# 2_interface.net
KiCad netlist of a schematic drawn in Altium Designer
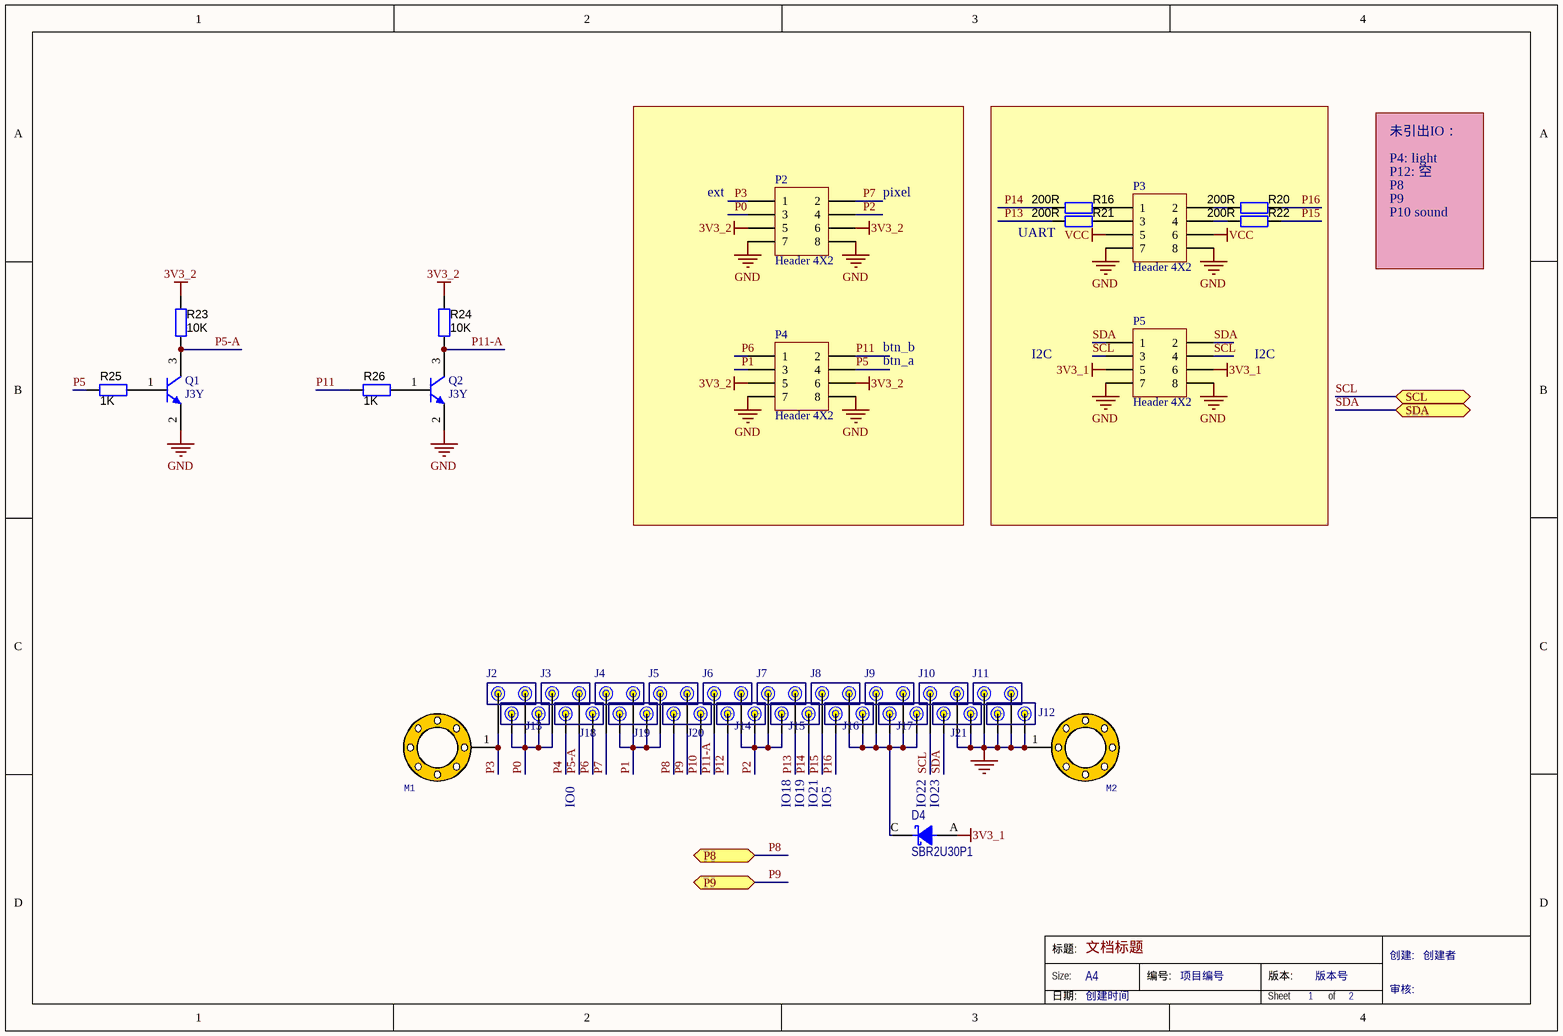
[diagram p0: 2.interface.SchDoc]

(export (version "E")
  (design (tool "Eeschema 10.0.6"))
  (components
    (comp (ref "D4")
      (value "SBR2U30P1")
      (footprint "POWERDI123")
      (fields (field (name "PARTNUMBER") "?") (field (name "PUBLISHER") "Altium Limited"))
      (libsource (lib "03.常用器件") (part "Diode_Schottky"))
    )
    (comp (ref "J2") (value "~") (footprint "顶针座子（2.54MM）") (libsource (lib "Schlib1") (part "pogopin")))
    (comp (ref "J3") (value "~") (footprint "顶针座子（2.54MM）") (libsource (lib "Schlib1") (part "pogopin")))
    (comp (ref "J4") (value "~") (footprint "顶针座子（2.54MM）") (libsource (lib "Schlib1") (part "pogopin")))
    (comp (ref "J5") (value "~") (footprint "顶针座子（2.54MM）") (libsource (lib "Schlib1") (part "pogopin")))
    (comp (ref "J6") (value "~") (footprint "顶针座子（2.54MM）") (libsource (lib "Schlib1") (part "pogopin")))
    (comp (ref "J7") (value "~") (footprint "顶针座子（2.54MM）") (libsource (lib "Schlib1") (part "pogopin")))
    (comp (ref "J8") (value "~") (footprint "顶针座子（2.54MM）") (libsource (lib "Schlib1") (part "pogopin")))
    (comp (ref "J9") (value "~") (footprint "顶针座子（2.54MM）") (libsource (lib "Schlib1") (part "pogopin")))
    (comp (ref "J10") (value "~") (footprint "顶针座子（2.54MM）") (libsource (lib "Schlib1") (part "pogopin")))
    (comp (ref "J11") (value "~") (footprint "顶针座子（2.54MM）") (libsource (lib "Schlib1") (part "pogopin")))
    (comp (ref "J12") (value "~") (footprint "顶针座子（2.54MM）") (libsource (lib "Schlib1") (part "pogopin_32")))
    (comp (ref "J13") (value "~") (footprint "顶针座子（2.54MM）") (libsource (lib "Schlib1") (part "pogopin_32")))
    (comp (ref "J14") (value "~") (footprint "顶针座子（2.54MM）") (libsource (lib "Schlib1") (part "pogopin_32")))
    (comp (ref "J15") (value "~") (footprint "顶针座子（2.54MM）") (libsource (lib "Schlib1") (part "pogopin_32")))
    (comp (ref "J16") (value "~") (footprint "顶针座子（2.54MM）") (libsource (lib "Schlib1") (part "pogopin_32")))
    (comp (ref "J17") (value "~") (footprint "顶针座子（2.54MM）") (libsource (lib "Schlib1") (part "pogopin_32")))
    (comp (ref "J18") (value "~") (footprint "顶针座子（2.54MM）") (libsource (lib "Schlib1") (part "pogopin_32")))
    (comp (ref "J19") (value "~") (footprint "顶针座子（2.54MM）") (libsource (lib "Schlib1") (part "pogopin_32")))
    (comp (ref "J20") (value "~") (footprint "顶针座子（2.54MM）") (libsource (lib "Schlib1") (part "pogopin_32")))
    (comp (ref "J21") (value "~") (footprint "顶针座子（2.54MM）") (libsource (lib "Schlib1") (part "pogopin_32")))
    (comp (ref "M1") (value "~") (footprint "3MM螺丝孔") (libsource (lib "labplus-connector") (part "screw")))
    (comp (ref "M2") (value "~") (footprint "3MM螺丝孔") (libsource (lib "labplus-connector") (part "screw")))
    (comp (ref "P2")
      (value "Header 4X2")
      (footprint "HDR2X4")
      (description "Header, 4-Pin, Dual row")
      (fields (field (name "PUBLISHER") "Altium Limited"))
      (libsource (lib "Miscellaneous Connectors") (part "Header 4X2"))
    )
    (comp (ref "P3")
      (value "Header 4X2")
      (footprint "HDR2X4")
      (description "Header, 4-Pin, Dual row")
      (fields (field (name "PUBLISHER") "Altium Limited"))
      (libsource (lib "Miscellaneous Connectors") (part "Header 4X2"))
    )
    (comp (ref "P4")
      (value "Header 4X2")
      (footprint "HDR2X4")
      (description "Header, 4-Pin, Dual row")
      (fields (field (name "PUBLISHER") "Altium Limited"))
      (libsource (lib "Miscellaneous Connectors") (part "Header 4X2"))
    )
    (comp (ref "P5")
      (value "Header 4X2")
      (footprint "HDR2X4")
      (description "Header, 4-Pin, Dual row")
      (fields (field (name "PUBLISHER") "Altium Limited"))
      (libsource (lib "Miscellaneous Connectors") (part "Header 4X2"))
    )
    (comp (ref "Q1")
      (value "J3Y")
      (footprint "DFN 3L")
      (description "NPN General Purpose Amplifier")
      (fields (field (name "PUBLISHER") "Altium Limited"))
      (libsource (lib "Schlib1") (part "2N3904"))
    )
    (comp (ref "Q2")
      (value "J3Y")
      (footprint "DFN 3L")
      (description "NPN General Purpose Amplifier")
      (fields (field (name "PUBLISHER") "Altium Limited"))
      (libsource (lib "Schlib1") (part "2N3904"))
    )
    (comp (ref "R16")
      (value "200R")
      (footprint "0402")
      (description "RES, 1.0k ohm, 5%, 0.1W, 0603")
      (fields
        (field (name "PARTNUMBER") "RC0603JR-071KL")
        (field (name "MANUFACTURER") "Yageo America")
        (field (name "PUBLISHER") "Texas Instruments")
      )
      (libsource (lib "") (part "RES1_1"))
    )
    (comp (ref "R20")
      (value "200R")
      (footprint "0402")
      (description "RES, 1.0k ohm, 5%, 0.1W, 0603")
      (fields
        (field (name "PARTNUMBER") "RC0603JR-071KL")
        (field (name "MANUFACTURER") "Yageo America")
        (field (name "PUBLISHER") "Texas Instruments")
      )
      (libsource (lib "") (part "RES1_1"))
    )
    (comp (ref "R21")
      (value "200R")
      (footprint "0402")
      (description "RES, 1.0k ohm, 5%, 0.1W, 0603")
      (fields
        (field (name "PARTNUMBER") "RC0603JR-071KL")
        (field (name "MANUFACTURER") "Yageo America")
        (field (name "PUBLISHER") "Texas Instruments")
      )
      (libsource (lib "") (part "RES1_1"))
    )
    (comp (ref "R22")
      (value "200R")
      (footprint "0402")
      (description "RES, 1.0k ohm, 5%, 0.1W, 0603")
      (fields
        (field (name "PARTNUMBER") "RC0603JR-071KL")
        (field (name "MANUFACTURER") "Yageo America")
        (field (name "PUBLISHER") "Texas Instruments")
      )
      (libsource (lib "") (part "RES1_1"))
    )
    (comp (ref "R23")
      (value "10K")
      (footprint "0402")
      (description "RES, 1.0k ohm, 5%, 0.1W, 0603")
      (fields
        (field (name "PARTNUMBER") "RC0603JR-071KL")
        (field (name "MANUFACTURER") "Yageo America")
        (field (name "PUBLISHER") "Texas Instruments")
      )
      (libsource (lib "03.常用器件") (part "RES1"))
    )
    (comp (ref "R24")
      (value "10K")
      (footprint "0402")
      (description "RES, 1.0k ohm, 5%, 0.1W, 0603")
      (fields
        (field (name "PARTNUMBER") "RC0603JR-071KL")
        (field (name "MANUFACTURER") "Yageo America")
        (field (name "PUBLISHER") "Texas Instruments")
      )
      (libsource (lib "03.常用器件") (part "RES1"))
    )
    (comp (ref "R25")
      (value "1K")
      (footprint "0402")
      (description "RES, 1.0k ohm, 5%, 0.1W, 0603")
      (fields
        (field (name "PARTNUMBER") "RC0603JR-071KL")
        (field (name "MANUFACTURER") "Yageo America")
        (field (name "PUBLISHER") "Texas Instruments")
      )
      (libsource (lib "") (part "RES1_2"))
    )
    (comp (ref "R26")
      (value "1K")
      (footprint "0402")
      (description "RES, 1.0k ohm, 5%, 0.1W, 0603")
      (fields
        (field (name "PARTNUMBER") "RC0603JR-071KL")
        (field (name "MANUFACTURER") "Yageo America")
        (field (name "PUBLISHER") "Texas Instruments")
      )
      (libsource (lib "") (part "RES1_2"))
    )
  )
  (nets
    (net (code "1") (name "/P0") (class "Default")
      (node (ref "J13") (pin "1") (pinfunction "1_1") (pintype "passive"))
      (node (ref "J13") (pin "2") (pinfunction "2_2") (pintype "passive"))
      (node (ref "J2") (pin "2") (pinfunction "2_2") (pintype "passive"))
      (node (ref "J3") (pin "1") (pinfunction "1_1") (pintype "passive"))
      (node (ref "P2") (pin "3") (pinfunction "3_3") (pintype "passive"))
    )
    (net (code "2") (name "/P1") (class "Default")
      (node (ref "J19") (pin "1") (pinfunction "1_1") (pintype "passive"))
      (node (ref "J19") (pin "2") (pinfunction "2_2") (pintype "passive"))
      (node (ref "J4") (pin "2") (pinfunction "2_2") (pintype "passive"))
      (node (ref "J5") (pin "1") (pinfunction "1_1") (pintype "passive"))
      (node (ref "P4") (pin "3") (pinfunction "3_3") (pintype "passive"))
    )
    (net (code "3") (name "/P2") (class "Default")
      (node (ref "J14") (pin "2") (pinfunction "2_2") (pintype "passive"))
      (node (ref "J15") (pin "1") (pinfunction "1_1") (pintype "passive"))
      (node (ref "J6") (pin "2") (pinfunction "2_2") (pintype "passive"))
      (node (ref "J7") (pin "1") (pinfunction "1_1") (pintype "passive"))
      (node (ref "P2") (pin "4") (pinfunction "4_4") (pintype "passive"))
    )
    (net (code "4") (name "/P3") (class "Default")
      (node (ref "J2") (pin "1") (pinfunction "1_1") (pintype "passive"))
      (node (ref "M1") (pin "1") (pinfunction "1_1") (pintype "passive"))
      (node (ref "P2") (pin "1") (pinfunction "1_1") (pintype "passive"))
    )
    (net (code "5") (name "/P4") (class "Default")
      (node (ref "J18") (pin "1") (pinfunction "1_1") (pintype "passive"))
    )
    (net (code "6") (name "/P5") (class "Default")
      (node (ref "P4") (pin "4") (pinfunction "4_4") (pintype "passive"))
      (node (ref "R25") (pin "1") (pinfunction "1_1") (pintype "passive"))
    )
    (net (code "7") (name "/P5-A") (class "Default")
      (node (ref "J3") (pin "2") (pinfunction "2_2") (pintype "passive"))
      (node (ref "Q1") (pin "3") (pinfunction "C_3") (pintype "passive"))
      (node (ref "R23") (pin "2") (pinfunction "2_2") (pintype "passive"))
    )
    (net (code "8") (name "/P6") (class "Default")
      (node (ref "J18") (pin "2") (pinfunction "2_2") (pintype "passive"))
      (node (ref "P4") (pin "1") (pinfunction "1_1") (pintype "passive"))
    )
    (net (code "9") (name "/P7") (class "Default")
      (node (ref "J4") (pin "1") (pinfunction "1_1") (pintype "passive"))
      (node (ref "P2") (pin "2") (pinfunction "2_2") (pintype "passive"))
    )
    (net (code "10") (name "/P8") (class "Default")
      (node (ref "J20") (pin "1") (pinfunction "1_1") (pintype "passive"))
    )
    (net (code "11") (name "/P9") (class "Default")
      (node (ref "J5") (pin "2") (pinfunction "2_2") (pintype "passive"))
    )
    (net (code "12") (name "/P10") (class "Default")
      (node (ref "J20") (pin "2") (pinfunction "2_2") (pintype "passive"))
    )
    (net (code "13") (name "/P11") (class "Default")
      (node (ref "P4") (pin "2") (pinfunction "2_2") (pintype "passive"))
      (node (ref "R26") (pin "1") (pinfunction "1_1") (pintype "passive"))
    )
    (net (code "14") (name "/P11-A") (class "Default")
      (node (ref "J6") (pin "1") (pinfunction "1_1") (pintype "passive"))
      (node (ref "Q2") (pin "3") (pinfunction "C_3") (pintype "passive"))
      (node (ref "R24") (pin "2") (pinfunction "2_2") (pintype "passive"))
    )
    (net (code "15") (name "/P12") (class "Default")
      (node (ref "J14") (pin "1") (pinfunction "1_1") (pintype "passive"))
    )
    (net (code "16") (name "/P13") (class "Default")
      (node (ref "J7") (pin "2") (pinfunction "2_2") (pintype "passive"))
      (node (ref "R21") (pin "1") (pinfunction "1_1") (pintype "passive"))
    )
    (net (code "17") (name "/P14") (class "Default")
      (node (ref "J15") (pin "2") (pinfunction "2_2") (pintype "passive"))
      (node (ref "R16") (pin "1") (pinfunction "1_1") (pintype "passive"))
    )
    (net (code "18") (name "/P15") (class "Default")
      (node (ref "J8") (pin "1") (pinfunction "1_1") (pintype "passive"))
      (node (ref "R22") (pin "2") (pinfunction "2_2") (pintype "passive"))
    )
    (net (code "19") (name "/P16") (class "Default")
      (node (ref "J16") (pin "1") (pinfunction "1_1") (pintype "passive"))
      (node (ref "R20") (pin "2") (pinfunction "2_2") (pintype "passive"))
    )
    (net (code "20") (name "/SCL") (class "Default")
      (node (ref "J10") (pin "1") (pinfunction "1_1") (pintype "passive"))
      (node (ref "P5") (pin "3") (pinfunction "3_3") (pintype "passive"))
      (node (ref "P5") (pin "4") (pinfunction "4_4") (pintype "passive"))
    )
    (net (code "21") (name "/SDA") (class "Default")
      (node (ref "J21") (pin "1") (pinfunction "1_1") (pintype "passive"))
      (node (ref "P5") (pin "1") (pinfunction "1_1") (pintype "passive"))
      (node (ref "P5") (pin "2") (pinfunction "2_2") (pintype "passive"))
    )
    (net (code "22") (name "3V3_1") (class "Default")
      (node (ref "D4") (pin "A") (pinfunction "ANODE_A") (pintype "passive"))
      (node (ref "P5") (pin "5") (pinfunction "5_5") (pintype "passive"))
      (node (ref "P5") (pin "6") (pinfunction "6_6") (pintype "passive"))
    )
    (net (code "23") (name "3V3_2") (class "Default")
      (node (ref "P2") (pin "5") (pinfunction "5_5") (pintype "passive"))
      (node (ref "P2") (pin "6") (pinfunction "6_6") (pintype "passive"))
      (node (ref "P4") (pin "5") (pinfunction "5_5") (pintype "passive"))
      (node (ref "P4") (pin "6") (pinfunction "6_6") (pintype "passive"))
      (node (ref "R23") (pin "1") (pinfunction "1_1") (pintype "passive"))
      (node (ref "R24") (pin "1") (pinfunction "1_1") (pintype "passive"))
    )
    (net (code "24") (name "GND") (class "Default")
      (node (ref "J10") (pin "2") (pinfunction "2_2") (pintype "passive"))
      (node (ref "J11") (pin "1") (pinfunction "1_1") (pintype "passive"))
      (node (ref "J11") (pin "2") (pinfunction "2_2") (pintype "passive"))
      (node (ref "J12") (pin "1") (pinfunction "1_1") (pintype "passive"))
      (node (ref "J12") (pin "2") (pinfunction "2_2") (pintype "passive"))
      (node (ref "J21") (pin "2") (pinfunction "2_2") (pintype "passive"))
      (node (ref "M2") (pin "1") (pinfunction "1_1") (pintype "passive"))
      (node (ref "P2") (pin "7") (pinfunction "7_7") (pintype "passive"))
      (node (ref "P2") (pin "8") (pinfunction "8_8") (pintype "passive"))
      (node (ref "P3") (pin "7") (pinfunction "7_7") (pintype "passive"))
      (node (ref "P3") (pin "8") (pinfunction "8_8") (pintype "passive"))
      (node (ref "P4") (pin "7") (pinfunction "7_7") (pintype "passive"))
      (node (ref "P4") (pin "8") (pinfunction "8_8") (pintype "passive"))
      (node (ref "P5") (pin "7") (pinfunction "7_7") (pintype "passive"))
      (node (ref "P5") (pin "8") (pinfunction "8_8") (pintype "passive"))
      (node (ref "Q1") (pin "2") (pinfunction "E_2") (pintype "passive"))
      (node (ref "Q2") (pin "2") (pinfunction "E_2") (pintype "passive"))
    )
    (net (code "25") (name "Net-(D4-CATHODE)") (class "Default")
      (node (ref "D4") (pin "C") (pinfunction "CATHODE_C") (pintype "passive"))
      (node (ref "J16") (pin "2") (pinfunction "2_2") (pintype "passive"))
      (node (ref "J17") (pin "1") (pinfunction "1_1") (pintype "passive"))
      (node (ref "J17") (pin "2") (pinfunction "2_2") (pintype "passive"))
      (node (ref "J8") (pin "2") (pinfunction "2_2") (pintype "passive"))
      (node (ref "J9") (pin "1") (pinfunction "1_1") (pintype "passive"))
      (node (ref "J9") (pin "2") (pinfunction "2_2") (pintype "passive"))
    )
    (net (code "26") (name "Net-(P3-Pad1)") (class "Default")
      (node (ref "P3") (pin "1") (pinfunction "1_1") (pintype "passive"))
      (node (ref "R16") (pin "2") (pinfunction "2_2") (pintype "passive"))
    )
    (net (code "27") (name "Net-(P3-Pad2)") (class "Default")
      (node (ref "P3") (pin "2") (pinfunction "2_2") (pintype "passive"))
      (node (ref "R20") (pin "1") (pinfunction "1_1") (pintype "passive"))
    )
    (net (code "28") (name "Net-(P3-Pad3)") (class "Default")
      (node (ref "P3") (pin "3") (pinfunction "3_3") (pintype "passive"))
      (node (ref "R21") (pin "2") (pinfunction "2_2") (pintype "passive"))
    )
    (net (code "29") (name "Net-(P3-Pad4)") (class "Default")
      (node (ref "P3") (pin "4") (pinfunction "4_4") (pintype "passive"))
      (node (ref "R22") (pin "1") (pinfunction "1_1") (pintype "passive"))
    )
    (net (code "30") (name "Net-(Q1-B)") (class "Default")
      (node (ref "Q1") (pin "1") (pinfunction "B_1") (pintype "passive"))
      (node (ref "R25") (pin "2") (pinfunction "2_2") (pintype "passive"))
    )
    (net (code "31") (name "Net-(Q2-B)") (class "Default")
      (node (ref "Q2") (pin "1") (pinfunction "B_1") (pintype "passive"))
      (node (ref "R26") (pin "2") (pinfunction "2_2") (pintype "passive"))
    )
    (net (code "32") (name "VCC") (class "Default")
      (node (ref "P3") (pin "5") (pinfunction "5_5") (pintype "passive"))
      (node (ref "P3") (pin "6") (pinfunction "6_6") (pintype "passive"))
    )
  )
)
